# USBA_SCH.net
KiCad netlist of a schematic drawn in EasyEDA
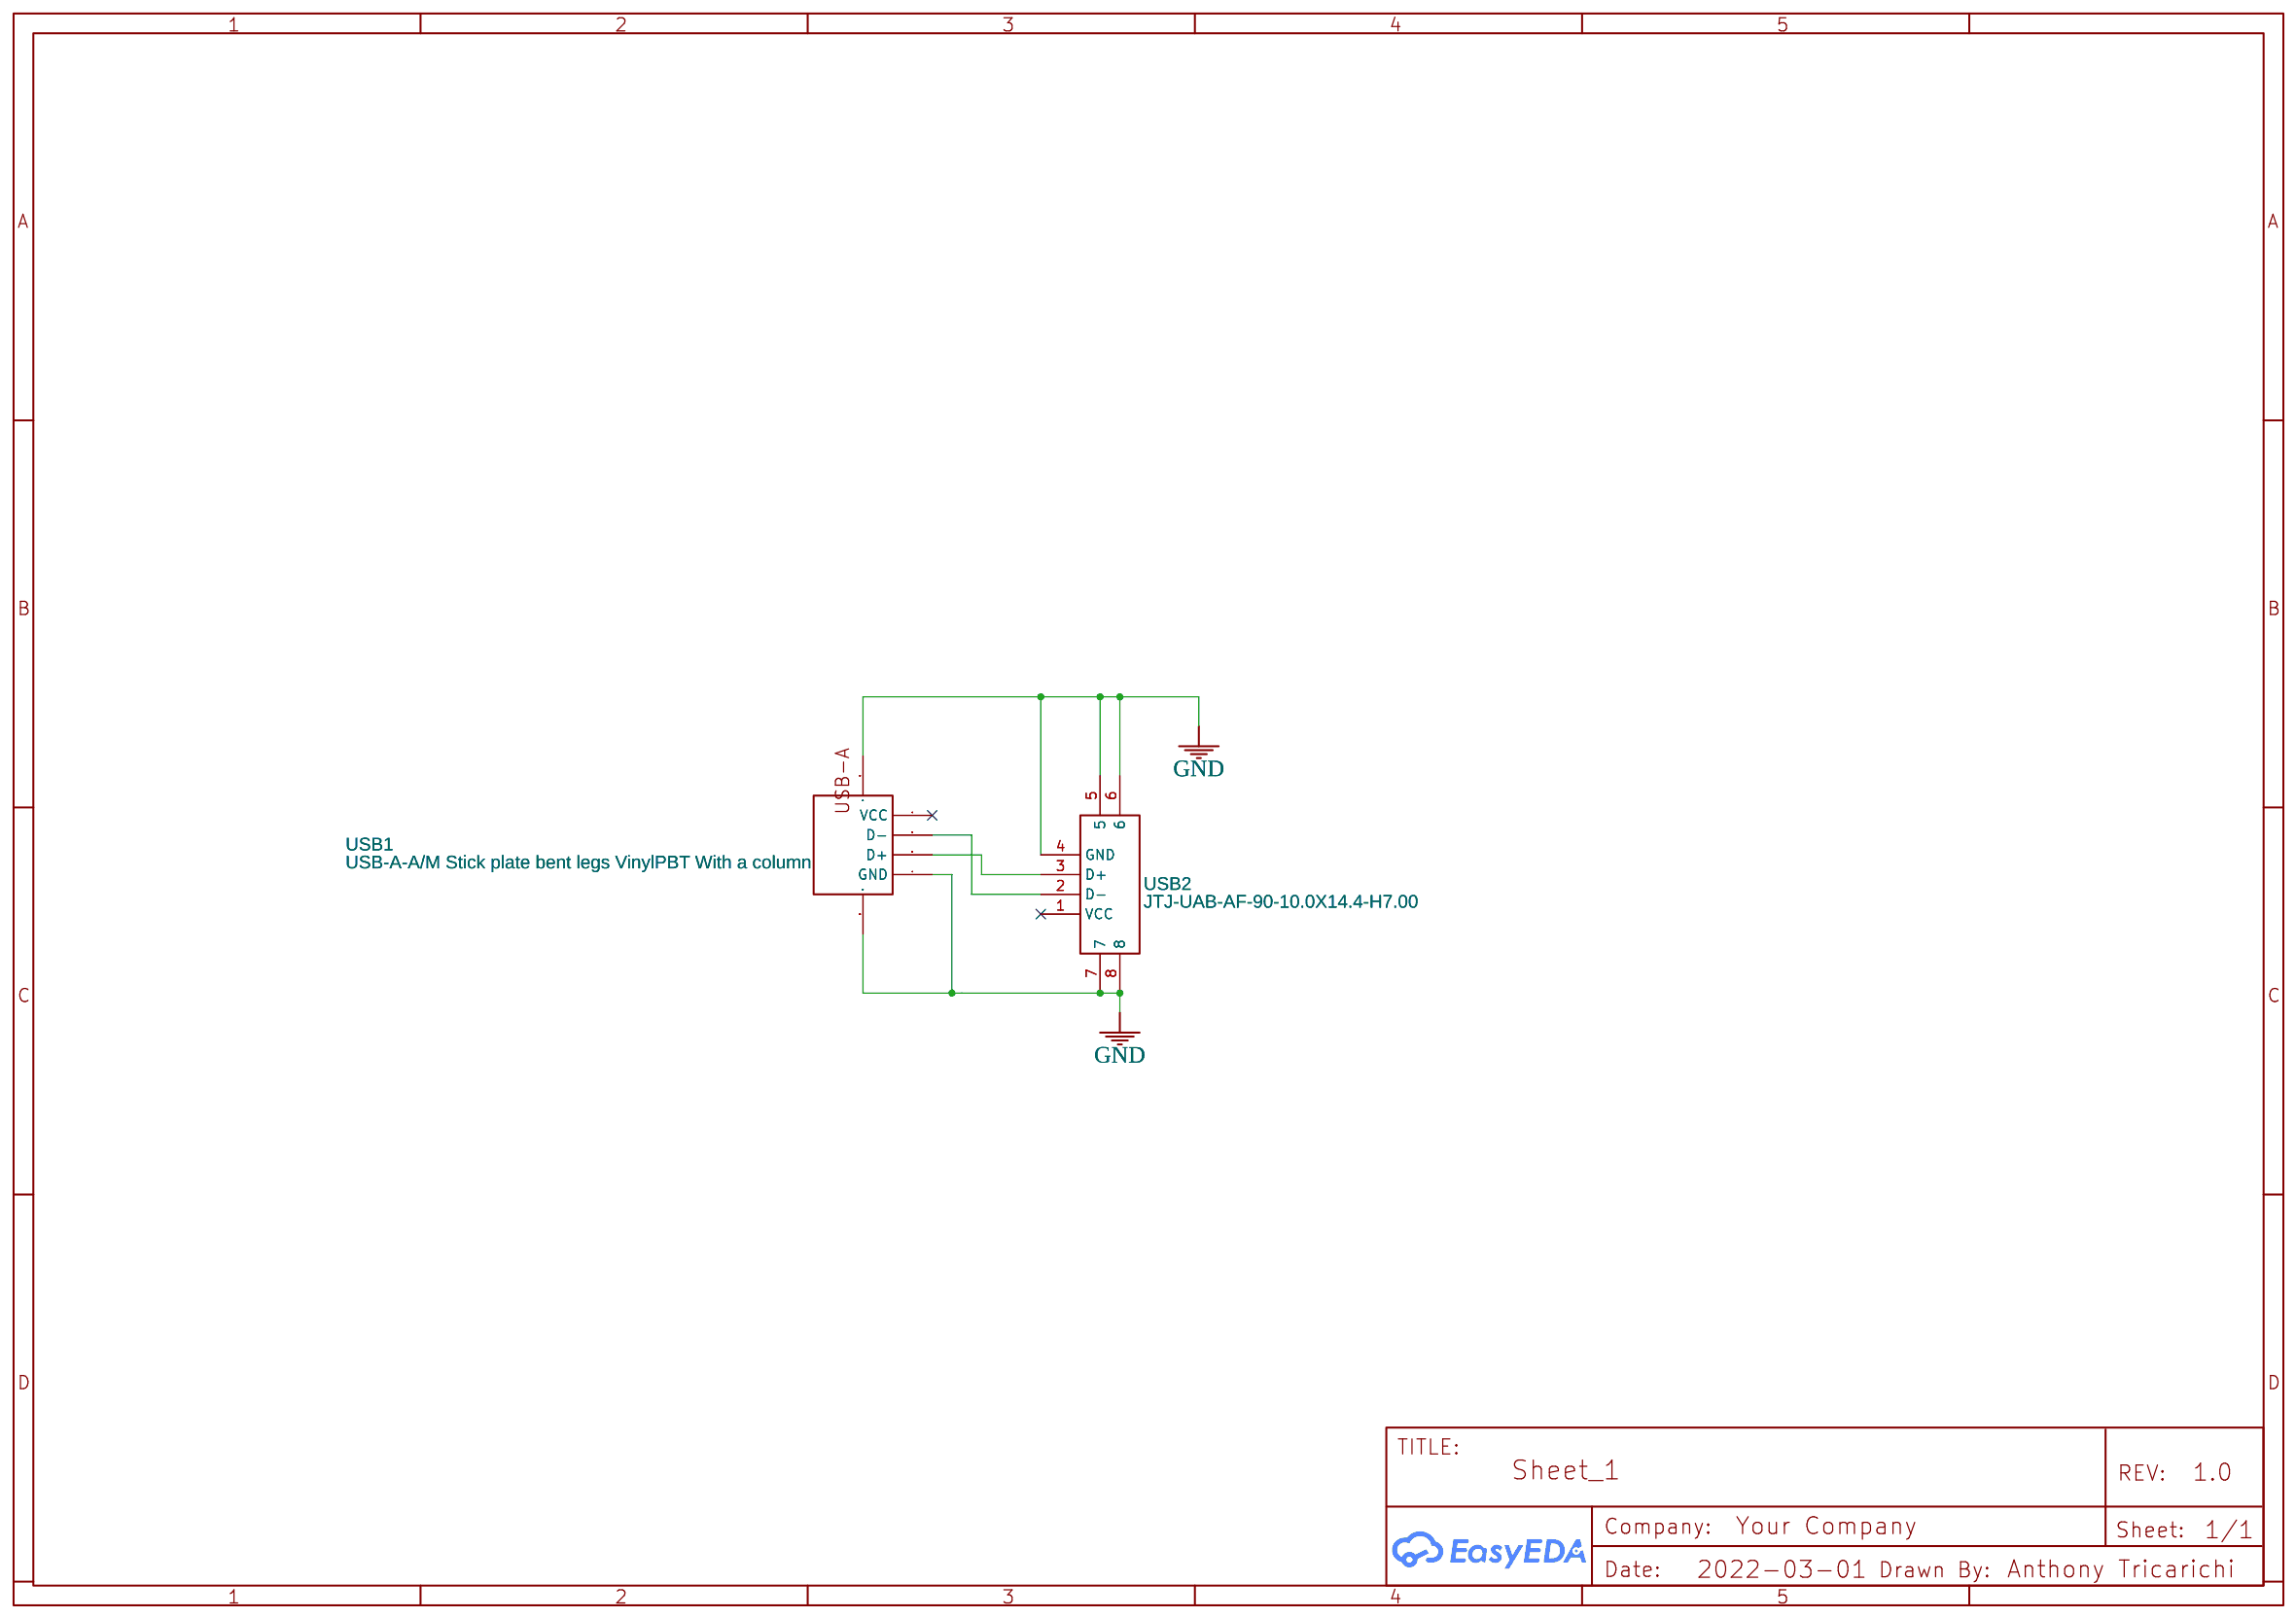
[diagram p0: schematic sheet]

(export (version "E")
  (design (tool "Eeschema 10.0.6"))
  (components
    (comp (ref "USB1")
      (value "USB-A-A/M Stick plate bent legs VinylPBT With a column")
      (fields
        (field (name "BOM_Manufacturer Part") "A/M Stick plate bent legs VinylPBT With a column")
        (field (name "BOM_Supplier Part") "C46394")
      )
      (libsource (lib "") (part "USB-A-A/M Stick plate bent legs VinylPBT With a column"))
    )
    (comp (ref "USB2")
      (value "JTJ-UAB-AF-90-10.0X14.4-H7.00")
      (fields (field (name "BOM_Supplier Part") "C42591"))
      (libsource (lib "") (part "JTJ-UAB-AF-90-10.0X14.4-H7.00"))
    )
  )
  (nets
    (net (code "1") (name "GND") (class "Default")
      (node (ref "USB1") (pin "4") (pinfunction "GND_4") (pintype "input"))
      (node (ref "USB1") (pin "5") (pinfunction "5_5") (pintype "unspecified"))
      (node (ref "USB1") (pin "6") (pinfunction "6_6") (pintype "unspecified"))
      (node (ref "USB2") (pin "4") (pinfunction "GND_4") (pintype "unspecified"))
      (node (ref "USB2") (pin "5") (pinfunction "5_5") (pintype "unspecified"))
      (node (ref "USB2") (pin "6") (pinfunction "6_6") (pintype "unspecified"))
      (node (ref "USB2") (pin "7") (pinfunction "7_7") (pintype "unspecified"))
      (node (ref "USB2") (pin "8") (pinfunction "8_8") (pintype "unspecified"))
    )
    (net (code "2") (name "Net-(USB1-D+)") (class "Default")
      (node (ref "USB1") (pin "3") (pinfunction "D+_3") (pintype "input"))
      (node (ref "USB2") (pin "3") (pinfunction "D+_3") (pintype "unspecified"))
    )
    (net (code "3") (name "Net-(USB1-D-)") (class "Default")
      (node (ref "USB1") (pin "2") (pinfunction "D-_2") (pintype "input"))
      (node (ref "USB2") (pin "2") (pinfunction "D-_2") (pintype "unspecified"))
    )
    (net (code "4") (name "unconnected-(USB1-VCC-Pad1)") (class "Default")
      (node (ref "USB1") (pin "1") (pinfunction "VCC_1") (pintype "input+no_connect"))
    )
    (net (code "5") (name "unconnected-(USB2-VCC-Pad1)") (class "Default")
      (node (ref "USB2") (pin "1") (pinfunction "VCC_1") (pintype "unspecified+no_connect"))
    )
  )
)
